# STM32F4_Schematics.net
KiCad netlist of a schematic drawn in Altium Designer
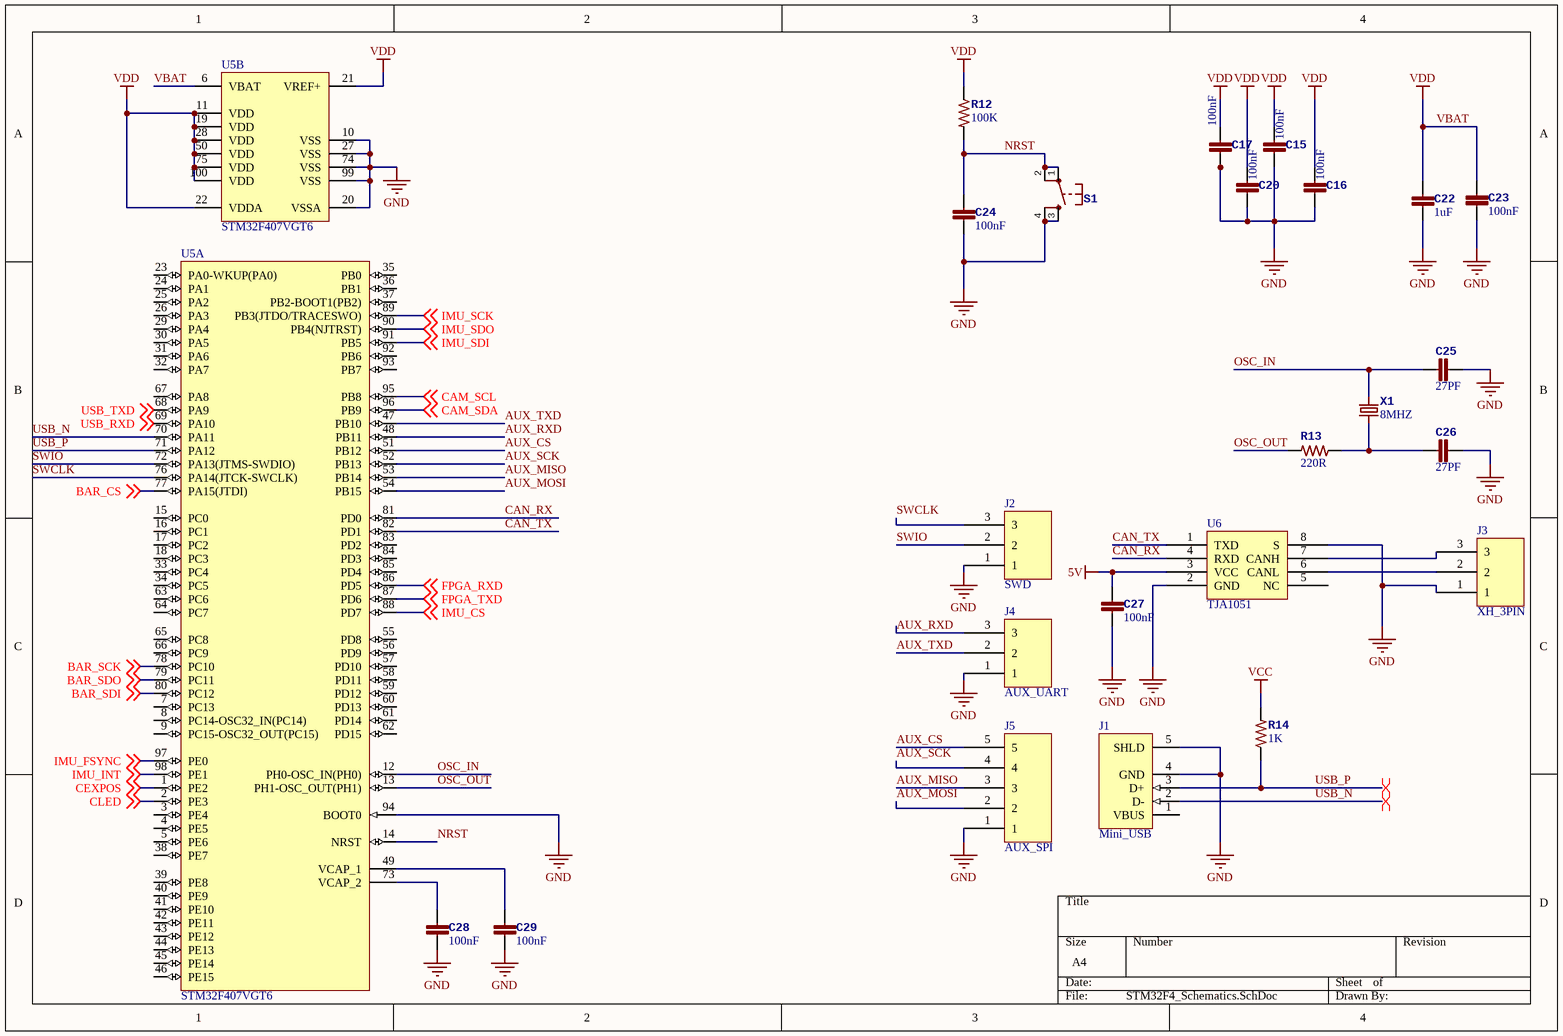
[diagram p0: STM32F4_Schematics.SchDoc]

(export (version "E")
  (design (tool "Eeschema 10.0.6"))
  (components
    (comp (ref "C15")
      (value "100nF")
      (footprint "_0805")
      (fields (field (name "Comment") "Cap"))
      (libsource (lib "Passives_Integrated_Library") (part "Cap_1"))
    )
    (comp (ref "C16")
      (value "100nF")
      (footprint "_0805")
      (fields (field (name "Comment") "Cap"))
      (libsource (lib "Passives_Integrated_Library") (part "Cap_1"))
    )
    (comp (ref "C17")
      (value "100nF")
      (footprint "_0805")
      (fields (field (name "Comment") "Cap"))
      (libsource (lib "Passives_Integrated_Library") (part "Cap_1"))
    )
    (comp (ref "C20")
      (value "100nF")
      (footprint "_0805")
      (fields (field (name "Comment") "Cap"))
      (libsource (lib "Passives_Integrated_Library") (part "Cap_1"))
    )
    (comp (ref "C22")
      (value "1uF")
      (footprint "_0805")
      (fields (field (name "Comment") "Cap"))
      (libsource (lib "Passives_Integrated_Library") (part "Cap_1"))
    )
    (comp (ref "C23")
      (value "100nF")
      (footprint "_0805")
      (fields (field (name "Comment") "Cap"))
      (libsource (lib "Passives_Integrated_Library") (part "Cap_1"))
    )
    (comp (ref "C24")
      (value "100nF")
      (footprint "_0805")
      (fields (field (name "Comment") "Cap"))
      (libsource (lib "") (part "Cap_1_1"))
    )
    (comp (ref "C25")
      (value "27PF")
      (footprint "_0805")
      (fields (field (name "Comment") "Cap"))
      (libsource (lib "") (part "Cap_1_2"))
    )
    (comp (ref "C26")
      (value "27PF")
      (footprint "_0805")
      (fields (field (name "Comment") "Cap"))
      (libsource (lib "") (part "Cap_1_2"))
    )
    (comp (ref "C27")
      (value "100nF")
      (footprint "_0805")
      (fields (field (name "Comment") "Cap"))
      (libsource (lib "Passives_Integrated_Library") (part "Cap_1"))
    )
    (comp (ref "C28")
      (value "100nF")
      (footprint "_0805")
      (fields (field (name "Comment") "Cap"))
      (libsource (lib "Passives_Integrated_Library") (part "Cap_1"))
    )
    (comp (ref "C29")
      (value "100nF")
      (footprint "_0805")
      (fields (field (name "Comment") "Cap"))
      (libsource (lib "Passives_Integrated_Library") (part "Cap_1"))
    )
    (comp (ref "J1")
      (value "Mini_USB")
      (footprint "My_USB")
      (description "USB 2.0, Right Angle, SMT, B Type, Receptacle, 5 Position, Black")
      (fields (field (name "PUBLISHER") "Altium Limited"))
      (libsource (lib "PC_Connectors_Integrated_Library") (part "Mini_USB"))
    )
    (comp (ref "J2")
      (value "SWD")
      (footprint "XH_3PIN")
      (libsource (lib "Others_Integrated_Library") (part "XH_3PIN"))
    )
    (comp (ref "J3")
      (value "XH_3PIN")
      (footprint "XH_3PIN")
      (libsource (lib "Others_Integrated_Library") (part "XH_3PIN"))
    )
    (comp (ref "J4")
      (value "AUX_UART")
      (footprint "XH_3PIN")
      (libsource (lib "Others_Integrated_Library") (part "XH_3PIN"))
    )
    (comp (ref "J5")
      (value "AUX_SPI")
      (footprint "XH_5PIN")
      (libsource (lib "Others_Integrated_Library") (part "XH_5PIN"))
    )
    (comp (ref "R12")
      (value "100K")
      (footprint "_0603")
      (fields (field (name "Comment") "Resistor"))
      (libsource (lib "Passives_Integrated_Library") (part "Resistor"))
    )
    (comp (ref "R13")
      (value "220R")
      (footprint "_0603")
      (fields (field (name "Comment") "Resistor"))
      (libsource (lib "Passives_Integrated_Library") (part "Resistor"))
    )
    (comp (ref "R14")
      (value "1K")
      (footprint "_0603")
      (fields (field (name "Comment") "Resistor"))
      (libsource (lib "Passives_Integrated_Library") (part "Resistor"))
    )
    (comp (ref "S1")
      (value "PushButton-4Pin")
      (footprint "_TACTILE_SWITCH_PTH_6.0MM")
      (libsource (lib "Miscellaneous_Integrated_Library") (part "PushButton-4Pin"))
    )
    (comp (ref "U5")
      (value "STM32F407VGT6")
      (footprint "STM-LQFP100_N")
      (fields (field (name "MANUFACTURER") "STMicroelectronics"))
      (libsource (lib "STMicroelectronics STM32 F4") (part "STM32F407VGT6"))
    )
    (comp (ref "U6")
      (value "TJA1051")
      (footprint "SO-8N")
      (libsource (lib "Transievers_Integrated_Library") (part "TJA1051"))
    )
    (comp (ref "X1")
      (value "8MHZ")
      (footprint "_CRYSTAL-HC49UP")
      (fields (field (name "Comment") "Crystal_1"))
      (libsource (lib "Passives_Integrated_Library") (part "Crystal_1"))
    )
  )
  (nets
    (net (code "1") (name "/AUX_CS") (class "Default")
      (node (ref "J5") (pin "5") (pinfunction "5_5") (pintype "passive"))
      (node (ref "U5") (pin "51") (pinfunction "PB12_51") (pintype "bidirectional"))
    )
    (net (code "2") (name "/AUX_MISO") (class "Default")
      (node (ref "J5") (pin "3") (pinfunction "3_3") (pintype "passive"))
      (node (ref "U5") (pin "53") (pinfunction "PB14_53") (pintype "bidirectional"))
    )
    (net (code "3") (name "/AUX_MOSI") (class "Default")
      (node (ref "J5") (pin "2") (pinfunction "2_2") (pintype "passive"))
      (node (ref "U5") (pin "54") (pinfunction "PB15_54") (pintype "bidirectional"))
    )
    (net (code "4") (name "/AUX_RXD") (class "Default")
      (node (ref "J4") (pin "3") (pinfunction "3_3") (pintype "passive"))
      (node (ref "U5") (pin "48") (pinfunction "PB11_48") (pintype "bidirectional"))
    )
    (net (code "5") (name "/AUX_SCK") (class "Default")
      (node (ref "J5") (pin "4") (pinfunction "4_4") (pintype "passive"))
      (node (ref "U5") (pin "52") (pinfunction "PB13_52") (pintype "bidirectional"))
    )
    (net (code "6") (name "/AUX_TXD") (class "Default")
      (node (ref "J4") (pin "2") (pinfunction "2_2") (pintype "passive"))
      (node (ref "U5") (pin "47") (pinfunction "PB10_47") (pintype "bidirectional"))
    )
    (net (code "7") (name "/CAN_RX") (class "Default")
      (node (ref "U5") (pin "81") (pinfunction "PD0_81") (pintype "bidirectional"))
      (node (ref "U6") (pin "4") (pinfunction "RXD_4") (pintype "passive"))
    )
    (net (code "8") (name "/CAN_TX") (class "Default")
      (node (ref "U5") (pin "82") (pinfunction "PD1_82") (pintype "bidirectional"))
      (node (ref "U6") (pin "1") (pinfunction "TXD_1") (pintype "passive"))
    )
    (net (code "9") (name "/NRST") (class "Default")
      (node (ref "C24") (pin "1") (pinfunction "1_1") (pintype "passive"))
      (node (ref "R12") (pin "2") (pinfunction "2_2") (pintype "passive"))
      (node (ref "S1") (pin "1") (pinfunction "1_1") (pintype "passive"))
      (node (ref "S1") (pin "2") (pinfunction "2_2") (pintype "passive"))
      (node (ref "U5") (pin "14") (pinfunction "NRST_14") (pintype "bidirectional"))
    )
    (net (code "10") (name "/OSC_IN") (class "Default")
      (node (ref "C25") (pin "1") (pinfunction "1_1") (pintype "passive"))
      (node (ref "U5") (pin "12") (pinfunction "PH0-OSC_IN(PH0)_12") (pintype "bidirectional"))
      (node (ref "X1") (pin "2") (pinfunction "2_2") (pintype "passive"))
    )
    (net (code "11") (name "/OSC_OUT") (class "Default")
      (node (ref "R13") (pin "2") (pinfunction "2_2") (pintype "passive"))
      (node (ref "U5") (pin "13") (pinfunction "PH1-OSC_OUT(PH1)_13") (pintype "bidirectional"))
    )
    (net (code "12") (name "/SWCLK") (class "Default")
      (node (ref "J2") (pin "3") (pinfunction "3_3") (pintype "passive"))
      (node (ref "U5") (pin "76") (pinfunction "PA14(JTCK-SWCLK)_76") (pintype "bidirectional"))
    )
    (net (code "13") (name "/SWIO") (class "Default")
      (node (ref "J2") (pin "2") (pinfunction "2_2") (pintype "passive"))
      (node (ref "U5") (pin "72") (pinfunction "PA13(JTMS-SWDIO)_72") (pintype "bidirectional"))
    )
    (net (code "14") (name "/USB_N") (class "Default")
      (node (ref "J1") (pin "2") (pinfunction "D-_2") (pintype "input"))
      (node (ref "U5") (pin "70") (pinfunction "PA11_70") (pintype "bidirectional"))
    )
    (net (code "15") (name "/USB_P") (class "Default")
      (node (ref "J1") (pin "3") (pinfunction "D+_3") (pintype "input"))
      (node (ref "R14") (pin "1") (pinfunction "1_1") (pintype "passive"))
      (node (ref "U5") (pin "71") (pinfunction "PA12_71") (pintype "bidirectional"))
    )
    (net (code "16") (name "5V") (class "Default")
      (node (ref "C27") (pin "2") (pinfunction "2_2") (pintype "passive"))
      (node (ref "U6") (pin "3") (pinfunction "VCC_3") (pintype "passive"))
    )
    (net (code "17") (name "BAR_CS") (class "Default")
      (node (ref "U5") (pin "77") (pinfunction "PA15(JTDI)_77") (pintype "bidirectional"))
    )
    (net (code "18") (name "BAR_SCK") (class "Default")
      (node (ref "U5") (pin "78") (pinfunction "PC10_78") (pintype "bidirectional"))
    )
    (net (code "19") (name "BAR_SDI") (class "Default")
      (node (ref "U5") (pin "80") (pinfunction "PC12_80") (pintype "bidirectional"))
    )
    (net (code "20") (name "BAR_SDO") (class "Default")
      (node (ref "U5") (pin "79") (pinfunction "PC11_79") (pintype "bidirectional"))
    )
    (net (code "21") (name "CAM_SCL") (class "Default")
      (node (ref "U5") (pin "95") (pinfunction "PB8_95") (pintype "bidirectional"))
    )
    (net (code "22") (name "CAM_SDA") (class "Default")
      (node (ref "U5") (pin "96") (pinfunction "PB9_96") (pintype "bidirectional"))
    )
    (net (code "23") (name "CEXPOS") (class "Default")
      (node (ref "U5") (pin "1") (pinfunction "PE2_1") (pintype "bidirectional"))
    )
    (net (code "24") (name "CLED") (class "Default")
      (node (ref "U5") (pin "2") (pinfunction "PE3_2") (pintype "bidirectional"))
    )
    (net (code "25") (name "FPGA_RXD") (class "Default")
      (node (ref "U5") (pin "86") (pinfunction "PD5_86") (pintype "bidirectional"))
    )
    (net (code "26") (name "FPGA_TXD") (class "Default")
      (node (ref "U5") (pin "87") (pinfunction "PD6_87") (pintype "bidirectional"))
    )
    (net (code "27") (name "GND") (class "Default")
      (node (ref "C15") (pin "1") (pinfunction "1_1") (pintype "passive"))
      (node (ref "C16") (pin "1") (pinfunction "1_1") (pintype "passive"))
      (node (ref "C17") (pin "1") (pinfunction "1_1") (pintype "passive"))
      (node (ref "C20") (pin "1") (pinfunction "1_1") (pintype "passive"))
      (node (ref "C22") (pin "1") (pinfunction "1_1") (pintype "passive"))
      (node (ref "C23") (pin "1") (pinfunction "1_1") (pintype "passive"))
      (node (ref "C24") (pin "2") (pinfunction "2_2") (pintype "passive"))
      (node (ref "C25") (pin "2") (pinfunction "2_2") (pintype "passive"))
      (node (ref "C26") (pin "2") (pinfunction "2_2") (pintype "passive"))
      (node (ref "C27") (pin "1") (pinfunction "1_1") (pintype "passive"))
      (node (ref "C28") (pin "1") (pinfunction "1_1") (pintype "passive"))
      (node (ref "C29") (pin "1") (pinfunction "1_1") (pintype "passive"))
      (node (ref "J1") (pin "4") (pinfunction "GND_4") (pintype "power_in"))
      (node (ref "J1") (pin "5") (pinfunction "SHLD_5") (pintype "passive"))
      (node (ref "J2") (pin "1") (pinfunction "1_1") (pintype "passive"))
      (node (ref "J3") (pin "1") (pinfunction "1_1") (pintype "passive"))
      (node (ref "J4") (pin "1") (pinfunction "1_1") (pintype "passive"))
      (node (ref "J5") (pin "1") (pinfunction "1_1") (pintype "passive"))
      (node (ref "S1") (pin "3") (pinfunction "3_3") (pintype "passive"))
      (node (ref "S1") (pin "4") (pinfunction "4_4") (pintype "passive"))
      (node (ref "U5") (pin "10") (pinfunction "VSS_10") (pintype "power_in"))
      (node (ref "U5") (pin "20") (pinfunction "VSSA_20") (pintype "power_in"))
      (node (ref "U5") (pin "27") (pinfunction "VSS_27") (pintype "power_in"))
      (node (ref "U5") (pin "74") (pinfunction "VSS_74") (pintype "power_in"))
      (node (ref "U5") (pin "94") (pinfunction "BOOT0_94") (pintype "input"))
      (node (ref "U5") (pin "99") (pinfunction "VSS_99") (pintype "power_in"))
      (node (ref "U6") (pin "2") (pinfunction "GND_2") (pintype "passive"))
      (node (ref "U6") (pin "8") (pinfunction "S_8") (pintype "passive"))
    )
    (net (code "28") (name "IMU_CS") (class "Default")
      (node (ref "U5") (pin "88") (pinfunction "PD7_88") (pintype "bidirectional"))
    )
    (net (code "29") (name "IMU_FSYNC") (class "Default")
      (node (ref "U5") (pin "97") (pinfunction "PE0_97") (pintype "bidirectional"))
    )
    (net (code "30") (name "IMU_INT") (class "Default")
      (node (ref "U5") (pin "98") (pinfunction "PE1_98") (pintype "bidirectional"))
    )
    (net (code "31") (name "IMU_SCK") (class "Default")
      (node (ref "U5") (pin "89") (pinfunction "PB3(JTDO/TRACESWO)_89") (pintype "bidirectional"))
    )
    (net (code "32") (name "IMU_SDI") (class "Default")
      (node (ref "U5") (pin "91") (pinfunction "PB5_91") (pintype "bidirectional"))
    )
    (net (code "33") (name "IMU_SDO") (class "Default")
      (node (ref "U5") (pin "90") (pinfunction "PB4(NJTRST)_90") (pintype "bidirectional"))
    )
    (net (code "34") (name "Net-(C26-Pad1)") (class "Default")
      (node (ref "C26") (pin "1") (pinfunction "1_1") (pintype "passive"))
      (node (ref "R13") (pin "1") (pinfunction "1_1") (pintype "passive"))
      (node (ref "X1") (pin "1") (pinfunction "1_1") (pintype "passive"))
    )
    (net (code "35") (name "Net-(U5A-VCAP_1)") (class "Default")
      (node (ref "C29") (pin "2") (pinfunction "2_2") (pintype "passive"))
      (node (ref "U5") (pin "49") (pinfunction "VCAP_1_49") (pintype "power_in"))
    )
    (net (code "36") (name "Net-(U5A-VCAP_2)") (class "Default")
      (node (ref "C28") (pin "2") (pinfunction "2_2") (pintype "passive"))
      (node (ref "U5") (pin "73") (pinfunction "VCAP_2_73") (pintype "power_in"))
    )
    (net (code "37") (name "Net-(U6-CANH)") (class "Default")
      (node (ref "J3") (pin "3") (pinfunction "3_3") (pintype "passive"))
      (node (ref "U6") (pin "7") (pinfunction "CANH_7") (pintype "passive"))
    )
    (net (code "38") (name "Net-(U6-CANL)") (class "Default")
      (node (ref "J3") (pin "2") (pinfunction "2_2") (pintype "passive"))
      (node (ref "U6") (pin "6") (pinfunction "CANL_6") (pintype "passive"))
    )
    (net (code "39") (name "USB_RXD") (class "Default")
      (node (ref "U5") (pin "69") (pinfunction "PA10_69") (pintype "bidirectional"))
    )
    (net (code "40") (name "USB_TXD") (class "Default")
      (node (ref "U5") (pin "68") (pinfunction "PA9_68") (pintype "bidirectional"))
    )
    (net (code "41") (name "VCC") (class "Default")
      (node (ref "R14") (pin "2") (pinfunction "2_2") (pintype "passive"))
    )
    (net (code "42") (name "VDD") (class "Default")
      (node (ref "C15") (pin "2") (pinfunction "2_2") (pintype "passive"))
      (node (ref "C16") (pin "2") (pinfunction "2_2") (pintype "passive"))
      (node (ref "C17") (pin "2") (pinfunction "2_2") (pintype "passive"))
      (node (ref "C20") (pin "2") (pinfunction "2_2") (pintype "passive"))
      (node (ref "C22") (pin "2") (pinfunction "2_2") (pintype "passive"))
      (node (ref "C23") (pin "2") (pinfunction "2_2") (pintype "passive"))
      (node (ref "R12") (pin "1") (pinfunction "1_1") (pintype "passive"))
      (node (ref "U5") (pin "100") (pinfunction "VDD_100") (pintype "power_in"))
      (node (ref "U5") (pin "11") (pinfunction "VDD_11") (pintype "power_in"))
      (node (ref "U5") (pin "19") (pinfunction "VDD_19") (pintype "power_in"))
      (node (ref "U5") (pin "21") (pinfunction "VREF+_21") (pintype "power_in"))
      (node (ref "U5") (pin "22") (pinfunction "VDDA_22") (pintype "power_in"))
      (node (ref "U5") (pin "28") (pinfunction "VDD_28") (pintype "power_in"))
      (node (ref "U5") (pin "50") (pinfunction "VDD_50") (pintype "power_in"))
      (node (ref "U5") (pin "6") (pinfunction "VBAT_6") (pintype "power_in"))
      (node (ref "U5") (pin "75") (pinfunction "VDD_75") (pintype "power_in"))
    )
    (net (code "43") (name "unconnected-(J1-VBUS-Pad1)") (class "Default")
      (node (ref "J1") (pin "1") (pinfunction "VBUS_1") (pintype "power_in"))
    )
    (net (code "44") (name "unconnected-(U5A-PA0-WKUP(PA0)-Pad23)") (class "Default")
      (node (ref "U5") (pin "23") (pinfunction "PA0-WKUP(PA0)_23") (pintype "bidirectional"))
    )
    (net (code "45") (name "unconnected-(U5A-PA1-Pad24)") (class "Default")
      (node (ref "U5") (pin "24") (pinfunction "PA1_24") (pintype "bidirectional"))
    )
    (net (code "46") (name "unconnected-(U5A-PA2-Pad25)") (class "Default")
      (node (ref "U5") (pin "25") (pinfunction "PA2_25") (pintype "bidirectional"))
    )
    (net (code "47") (name "unconnected-(U5A-PA3-Pad26)") (class "Default")
      (node (ref "U5") (pin "26") (pinfunction "PA3_26") (pintype "bidirectional"))
    )
    (net (code "48") (name "unconnected-(U5A-PA4-Pad29)") (class "Default")
      (node (ref "U5") (pin "29") (pinfunction "PA4_29") (pintype "bidirectional"))
    )
    (net (code "49") (name "unconnected-(U5A-PA5-Pad30)") (class "Default")
      (node (ref "U5") (pin "30") (pinfunction "PA5_30") (pintype "bidirectional"))
    )
    (net (code "50") (name "unconnected-(U5A-PA6-Pad31)") (class "Default")
      (node (ref "U5") (pin "31") (pinfunction "PA6_31") (pintype "bidirectional"))
    )
    (net (code "51") (name "unconnected-(U5A-PA7-Pad32)") (class "Default")
      (node (ref "U5") (pin "32") (pinfunction "PA7_32") (pintype "bidirectional"))
    )
    (net (code "52") (name "unconnected-(U5A-PA8-Pad67)") (class "Default")
      (node (ref "U5") (pin "67") (pinfunction "PA8_67") (pintype "bidirectional"))
    )
    (net (code "53") (name "unconnected-(U5A-PB0-Pad35)") (class "Default")
      (node (ref "U5") (pin "35") (pinfunction "PB0_35") (pintype "bidirectional"))
    )
    (net (code "54") (name "unconnected-(U5A-PB1-Pad36)") (class "Default")
      (node (ref "U5") (pin "36") (pinfunction "PB1_36") (pintype "bidirectional"))
    )
    (net (code "55") (name "unconnected-(U5A-PB2-BOOT1(PB2)-Pad37)") (class "Default")
      (node (ref "U5") (pin "37") (pinfunction "PB2-BOOT1(PB2)_37") (pintype "bidirectional"))
    )
    (net (code "56") (name "unconnected-(U5A-PB6-Pad92)") (class "Default")
      (node (ref "U5") (pin "92") (pinfunction "PB6_92") (pintype "bidirectional"))
    )
    (net (code "57") (name "unconnected-(U5A-PB7-Pad93)") (class "Default")
      (node (ref "U5") (pin "93") (pinfunction "PB7_93") (pintype "bidirectional"))
    )
    (net (code "58") (name "unconnected-(U5A-PC0-Pad15)") (class "Default")
      (node (ref "U5") (pin "15") (pinfunction "PC0_15") (pintype "bidirectional"))
    )
    (net (code "59") (name "unconnected-(U5A-PC1-Pad16)") (class "Default")
      (node (ref "U5") (pin "16") (pinfunction "PC1_16") (pintype "bidirectional"))
    )
    (net (code "60") (name "unconnected-(U5A-PC2-Pad17)") (class "Default")
      (node (ref "U5") (pin "17") (pinfunction "PC2_17") (pintype "bidirectional"))
    )
    (net (code "61") (name "unconnected-(U5A-PC3-Pad18)") (class "Default")
      (node (ref "U5") (pin "18") (pinfunction "PC3_18") (pintype "bidirectional"))
    )
    (net (code "62") (name "unconnected-(U5A-PC4-Pad33)") (class "Default")
      (node (ref "U5") (pin "33") (pinfunction "PC4_33") (pintype "bidirectional"))
    )
    (net (code "63") (name "unconnected-(U5A-PC5-Pad34)") (class "Default")
      (node (ref "U5") (pin "34") (pinfunction "PC5_34") (pintype "bidirectional"))
    )
    (net (code "64") (name "unconnected-(U5A-PC6-Pad63)") (class "Default")
      (node (ref "U5") (pin "63") (pinfunction "PC6_63") (pintype "bidirectional"))
    )
    (net (code "65") (name "unconnected-(U5A-PC7-Pad64)") (class "Default")
      (node (ref "U5") (pin "64") (pinfunction "PC7_64") (pintype "bidirectional"))
    )
    (net (code "66") (name "unconnected-(U5A-PC8-Pad65)") (class "Default")
      (node (ref "U5") (pin "65") (pinfunction "PC8_65") (pintype "bidirectional"))
    )
    (net (code "67") (name "unconnected-(U5A-PC9-Pad66)") (class "Default")
      (node (ref "U5") (pin "66") (pinfunction "PC9_66") (pintype "bidirectional"))
    )
    (net (code "68") (name "unconnected-(U5A-PC13-Pad7)") (class "Default")
      (node (ref "U5") (pin "7") (pinfunction "PC13_7") (pintype "bidirectional"))
    )
    (net (code "69") (name "unconnected-(U5A-PC14-OSC32_IN(PC14)-Pad8)") (class "Default")
      (node (ref "U5") (pin "8") (pinfunction "PC14-OSC32_IN(PC14)_8") (pintype "bidirectional"))
    )
    (net (code "70") (name "unconnected-(U5A-PC15-OSC32_OUT(PC15)-Pad9)") (class "Default")
      (node (ref "U5") (pin "9") (pinfunction "PC15-OSC32_OUT(PC15)_9") (pintype "bidirectional"))
    )
    (net (code "71") (name "unconnected-(U5A-PD2-Pad83)") (class "Default")
      (node (ref "U5") (pin "83") (pinfunction "PD2_83") (pintype "bidirectional"))
    )
    (net (code "72") (name "unconnected-(U5A-PD3-Pad84)") (class "Default")
      (node (ref "U5") (pin "84") (pinfunction "PD3_84") (pintype "bidirectional"))
    )
    (net (code "73") (name "unconnected-(U5A-PD4-Pad85)") (class "Default")
      (node (ref "U5") (pin "85") (pinfunction "PD4_85") (pintype "bidirectional"))
    )
    (net (code "74") (name "unconnected-(U5A-PD8-Pad55)") (class "Default")
      (node (ref "U5") (pin "55") (pinfunction "PD8_55") (pintype "bidirectional"))
    )
    (net (code "75") (name "unconnected-(U5A-PD9-Pad56)") (class "Default")
      (node (ref "U5") (pin "56") (pinfunction "PD9_56") (pintype "bidirectional"))
    )
    (net (code "76") (name "unconnected-(U5A-PD10-Pad57)") (class "Default")
      (node (ref "U5") (pin "57") (pinfunction "PD10_57") (pintype "bidirectional"))
    )
    (net (code "77") (name "unconnected-(U5A-PD11-Pad58)") (class "Default")
      (node (ref "U5") (pin "58") (pinfunction "PD11_58") (pintype "bidirectional"))
    )
    (net (code "78") (name "unconnected-(U5A-PD12-Pad59)") (class "Default")
      (node (ref "U5") (pin "59") (pinfunction "PD12_59") (pintype "bidirectional"))
    )
    (net (code "79") (name "unconnected-(U5A-PD13-Pad60)") (class "Default")
      (node (ref "U5") (pin "60") (pinfunction "PD13_60") (pintype "bidirectional"))
    )
    (net (code "80") (name "unconnected-(U5A-PD14-Pad61)") (class "Default")
      (node (ref "U5") (pin "61") (pinfunction "PD14_61") (pintype "bidirectional"))
    )
    (net (code "81") (name "unconnected-(U5A-PD15-Pad62)") (class "Default")
      (node (ref "U5") (pin "62") (pinfunction "PD15_62") (pintype "bidirectional"))
    )
    (net (code "82") (name "unconnected-(U5A-PE4-Pad3)") (class "Default")
      (node (ref "U5") (pin "3") (pinfunction "PE4_3") (pintype "bidirectional"))
    )
    (net (code "83") (name "unconnected-(U5A-PE5-Pad4)") (class "Default")
      (node (ref "U5") (pin "4") (pinfunction "PE5_4") (pintype "bidirectional"))
    )
    (net (code "84") (name "unconnected-(U5A-PE6-Pad5)") (class "Default")
      (node (ref "U5") (pin "5") (pinfunction "PE6_5") (pintype "bidirectional"))
    )
    (net (code "85") (name "unconnected-(U5A-PE7-Pad38)") (class "Default")
      (node (ref "U5") (pin "38") (pinfunction "PE7_38") (pintype "bidirectional"))
    )
    (net (code "86") (name "unconnected-(U5A-PE8-Pad39)") (class "Default")
      (node (ref "U5") (pin "39") (pinfunction "PE8_39") (pintype "bidirectional"))
    )
    (net (code "87") (name "unconnected-(U5A-PE9-Pad40)") (class "Default")
      (node (ref "U5") (pin "40") (pinfunction "PE9_40") (pintype "bidirectional"))
    )
    (net (code "88") (name "unconnected-(U5A-PE10-Pad41)") (class "Default")
      (node (ref "U5") (pin "41") (pinfunction "PE10_41") (pintype "bidirectional"))
    )
    (net (code "89") (name "unconnected-(U5A-PE11-Pad42)") (class "Default")
      (node (ref "U5") (pin "42") (pinfunction "PE11_42") (pintype "bidirectional"))
    )
    (net (code "90") (name "unconnected-(U5A-PE12-Pad43)") (class "Default")
      (node (ref "U5") (pin "43") (pinfunction "PE12_43") (pintype "bidirectional"))
    )
    (net (code "91") (name "unconnected-(U5A-PE13-Pad44)") (class "Default")
      (node (ref "U5") (pin "44") (pinfunction "PE13_44") (pintype "bidirectional"))
    )
    (net (code "92") (name "unconnected-(U5A-PE14-Pad45)") (class "Default")
      (node (ref "U5") (pin "45") (pinfunction "PE14_45") (pintype "bidirectional"))
    )
    (net (code "93") (name "unconnected-(U5A-PE15-Pad46)") (class "Default")
      (node (ref "U5") (pin "46") (pinfunction "PE15_46") (pintype "bidirectional"))
    )
    (net (code "94") (name "unconnected-(U6-NC-Pad5)") (class "Default")
      (node (ref "U6") (pin "5") (pinfunction "NC_5") (pintype "passive"))
    )
  )
)
